# controller.net
KiCad netlist of a schematic drawn in EAGLE
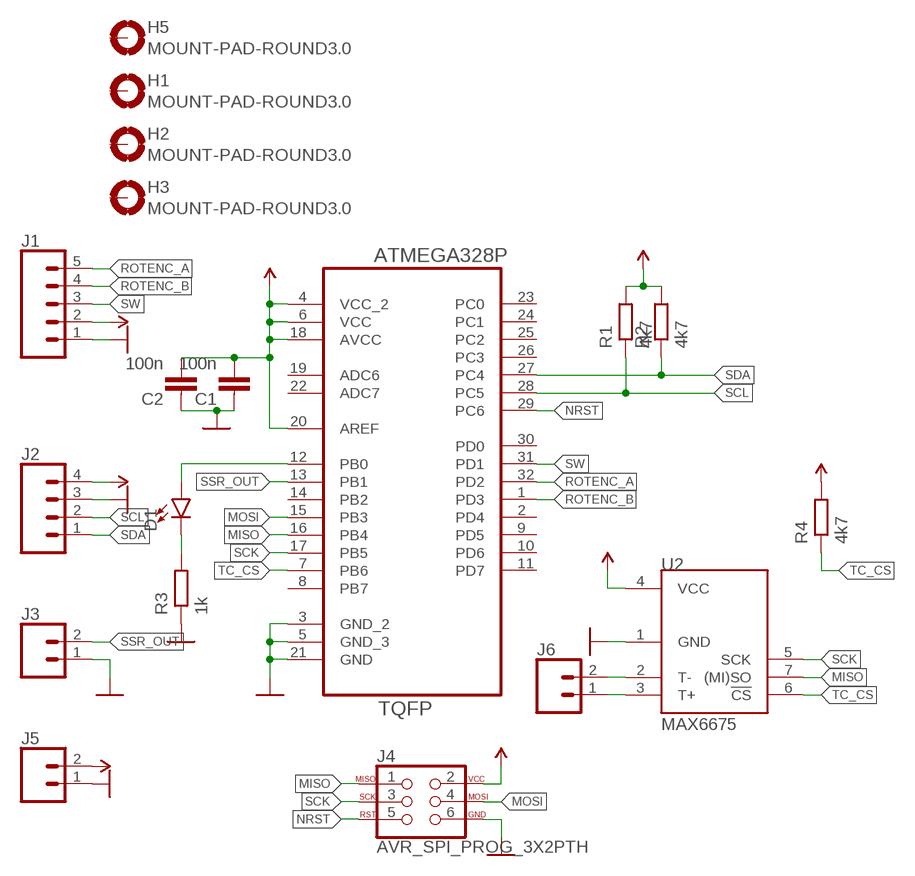
[diagram p0: schematic, sheet 1]

(export (version "E")
  (design (tool "Eeschema 10.0.6"))
  (components
    (comp (ref "C1")
      (value "100n")
      (footprint "eagle-import:C0603-N")
      (libsource (lib "eagle-import") (part "CAPACITOR0603-N"))
    )
    (comp (ref "C2")
      (value "100n")
      (footprint "eagle-import:C0603-N")
      (libsource (lib "eagle-import") (part "CAPACITOR0603-N"))
    )
    (comp (ref "D1")
      (value "LED0603")
      (footprint "eagle-import:LED-0603")
      (libsource (lib "eagle-import") (part "LED0603"))
    )
    (comp (ref "H1")
      (value "MOUNT-PAD-ROUND3.0")
      (footprint "eagle-import:3,0-PAD")
      (libsource (lib "eagle-import") (part "MOUNT-PAD-ROUND3.0"))
    )
    (comp (ref "H2")
      (value "MOUNT-PAD-ROUND3.0")
      (footprint "eagle-import:3,0-PAD")
      (libsource (lib "eagle-import") (part "MOUNT-PAD-ROUND3.0"))
    )
    (comp (ref "H3")
      (value "MOUNT-PAD-ROUND3.0")
      (footprint "eagle-import:3,0-PAD")
      (libsource (lib "eagle-import") (part "MOUNT-PAD-ROUND3.0"))
    )
    (comp (ref "H5")
      (value "MOUNT-PAD-ROUND3.0")
      (footprint "eagle-import:3,0-PAD")
      (libsource (lib "eagle-import") (part "MOUNT-PAD-ROUND3.0"))
    )
    (comp (ref "J1")
      (value "CONN_05PTH_LONGPADS")
      (footprint "eagle-import:1X05_LONGPADS")
      (libsource (lib "eagle-import") (part "CONN_05PTH_LONGPADS"))
    )
    (comp (ref "J2")
      (value "CONN_04LONGPADS")
      (footprint "eagle-import:1X04_LONGPADS")
      (libsource (lib "eagle-import") (part "CONN_04LONGPADS"))
    )
    (comp (ref "J3")
      (value "CONN_02PTH3")
      (footprint "eagle-import:1X02_LONGPADS")
      (libsource (lib "eagle-import") (part "CONN_02PTH3"))
    )
    (comp (ref "J4")
      (value "AVR_SPI_PROG_3X2PTH")
      (footprint "eagle-import:2X3")
      (libsource (lib "eagle-import") (part "AVR_SPI_PROG_3X2PTH"))
    )
    (comp (ref "J5")
      (value "CONN_02PTH3")
      (footprint "eagle-import:1X02_LONGPADS")
      (libsource (lib "eagle-import") (part "CONN_02PTH3"))
    )
    (comp (ref "J6")
      (value "CONN_02PTH3")
      (footprint "eagle-import:1X02_LONGPADS")
      (libsource (lib "eagle-import") (part "CONN_02PTH3"))
    )
    (comp (ref "R1")
      (value "4k7")
      (footprint "eagle-import:R0603-N")
      (libsource (lib "eagle-import") (part "RESISTOR0603-N"))
    )
    (comp (ref "R2")
      (value "4k7")
      (footprint "eagle-import:R0603-N")
      (libsource (lib "eagle-import") (part "RESISTOR0603-N"))
    )
    (comp (ref "R3")
      (value "1k")
      (footprint "eagle-import:R0603-N")
      (libsource (lib "eagle-import") (part "RESISTOR0603-N"))
    )
    (comp (ref "R4")
      (value "4k7")
      (footprint "eagle-import:R0603-N")
      (libsource (lib "eagle-import") (part "RESISTOR0603-N"))
    )
    (comp (ref "U1")
      (value "ATMEGA328P-AU")
      (footprint "eagle-import:QFP80P900X900X120-32N")
      (libsource (lib "eagle-import") (part "ATMEGA328P-AU"))
    )
    (comp (ref "U2")
      (value "MAX6675")
      (footprint "eagle-import:SOIC8")
      (libsource (lib "eagle-import") (part "MAX6675"))
    )
  )
  (nets
    (net (code "1") (name "GND") (class "Default")
      (node (ref "C1") (pin "1") (pinfunction "1_1") (pintype "passive"))
      (node (ref "C2") (pin "1") (pinfunction "1_1") (pintype "passive"))
      (node (ref "J1") (pin "1") (pinfunction "1_1") (pintype "passive"))
      (node (ref "J2") (pin "3") (pinfunction "3_3") (pintype "passive"))
      (node (ref "J3") (pin "1") (pinfunction "1_1") (pintype "passive"))
      (node (ref "J4") (pin "6") (pinfunction "6_6") (pintype "passive"))
      (node (ref "J5") (pin "1") (pinfunction "1_1") (pintype "passive"))
      (node (ref "R3") (pin "1") (pinfunction "P$1_1") (pintype "passive"))
      (node (ref "U1") (pin "21") (pinfunction "GND_21") (pintype "passive"))
      (node (ref "U1") (pin "3") (pinfunction "GND_2_3") (pintype "passive"))
      (node (ref "U1") (pin "5") (pinfunction "GND_3_5") (pintype "passive"))
      (node (ref "U2") (pin "1") (pinfunction "GND_1") (pintype "bidirectional"))
    )
    (net (code "2") (name "MISO") (class "Default")
      (node (ref "J4") (pin "1") (pinfunction "1_1") (pintype "passive"))
      (node (ref "U1") (pin "16") (pinfunction "PB4_16") (pintype "bidirectional"))
      (node (ref "U2") (pin "7") (pinfunction "(MI)SO_7") (pintype "bidirectional"))
    )
    (net (code "3") (name "MOSI") (class "Default")
      (node (ref "J4") (pin "4") (pinfunction "4_4") (pintype "passive"))
      (node (ref "U1") (pin "15") (pinfunction "PB3_15") (pintype "bidirectional"))
    )
    (net (code "4") (name "NRST") (class "Default")
      (node (ref "J4") (pin "5") (pinfunction "5_5") (pintype "passive"))
      (node (ref "U1") (pin "29") (pinfunction "PC6_29") (pintype "bidirectional"))
    )
    (net (code "5") (name "Net-(R3-P$2)") (class "Default")
      (node (ref "D1") (pin "C") (pinfunction "C_C") (pintype "passive"))
      (node (ref "R3") (pin "2") (pinfunction "P$2_2") (pintype "passive"))
    )
    (net (code "6") (name "Net-(U1-PB0)") (class "Default")
      (node (ref "D1") (pin "A") (pinfunction "A_A") (pintype "passive"))
      (node (ref "U1") (pin "12") (pinfunction "PB0_12") (pintype "bidirectional"))
    )
    (net (code "7") (name "Net-(U2-T+)") (class "Default")
      (node (ref "J6") (pin "1") (pinfunction "1_1") (pintype "passive"))
      (node (ref "U2") (pin "3") (pinfunction "T+_3") (pintype "bidirectional"))
    )
    (net (code "8") (name "Net-(U2-T-)") (class "Default")
      (node (ref "J6") (pin "2") (pinfunction "2_2") (pintype "passive"))
      (node (ref "U2") (pin "2") (pinfunction "T-_2") (pintype "bidirectional"))
    )
    (net (code "9") (name "ROTENC_A") (class "Default")
      (node (ref "J1") (pin "5") (pinfunction "5_5") (pintype "passive"))
      (node (ref "U1") (pin "32") (pinfunction "PD2_32") (pintype "bidirectional"))
    )
    (net (code "10") (name "ROTENC_B") (class "Default")
      (node (ref "J1") (pin "4") (pinfunction "4_4") (pintype "passive"))
      (node (ref "U1") (pin "1") (pinfunction "PD3_1") (pintype "bidirectional"))
    )
    (net (code "11") (name "SCK") (class "Default")
      (node (ref "J4") (pin "3") (pinfunction "3_3") (pintype "passive"))
      (node (ref "U1") (pin "17") (pinfunction "PB5_17") (pintype "bidirectional"))
      (node (ref "U2") (pin "5") (pinfunction "SCK_5") (pintype "bidirectional"))
    )
    (net (code "12") (name "SCL") (class "Default")
      (node (ref "J2") (pin "2") (pinfunction "2_2") (pintype "passive"))
      (node (ref "R1") (pin "1") (pinfunction "P$1_1") (pintype "passive"))
      (node (ref "U1") (pin "28") (pinfunction "PC5_28") (pintype "bidirectional"))
    )
    (net (code "13") (name "SDA") (class "Default")
      (node (ref "J2") (pin "1") (pinfunction "1_1") (pintype "passive"))
      (node (ref "R2") (pin "1") (pinfunction "P$1_1") (pintype "passive"))
      (node (ref "U1") (pin "27") (pinfunction "PC4_27") (pintype "bidirectional"))
    )
    (net (code "14") (name "SSR_OUT") (class "Default")
      (node (ref "J3") (pin "2") (pinfunction "2_2") (pintype "passive"))
      (node (ref "U1") (pin "13") (pinfunction "PB1_13") (pintype "bidirectional"))
    )
    (net (code "15") (name "SW") (class "Default")
      (node (ref "J1") (pin "3") (pinfunction "3_3") (pintype "passive"))
      (node (ref "U1") (pin "31") (pinfunction "PD1_31") (pintype "bidirectional"))
    )
    (net (code "16") (name "TC_CS") (class "Default")
      (node (ref "R4") (pin "1") (pinfunction "P$1_1") (pintype "passive"))
      (node (ref "U1") (pin "7") (pinfunction "PB6_7") (pintype "bidirectional"))
      (node (ref "U2") (pin "6") (pinfunction "~{CS}_6") (pintype "bidirectional"))
    )
    (net (code "17") (name "VCC") (class "Default")
      (node (ref "C1") (pin "2") (pinfunction "2_2") (pintype "passive"))
      (node (ref "C2") (pin "2") (pinfunction "2_2") (pintype "passive"))
      (node (ref "J1") (pin "2") (pinfunction "2_2") (pintype "passive"))
      (node (ref "J2") (pin "4") (pinfunction "4_4") (pintype "passive"))
      (node (ref "J4") (pin "2") (pinfunction "2_2") (pintype "passive"))
      (node (ref "J5") (pin "2") (pinfunction "2_2") (pintype "passive"))
      (node (ref "R1") (pin "2") (pinfunction "P$2_2") (pintype "passive"))
      (node (ref "R2") (pin "2") (pinfunction "P$2_2") (pintype "passive"))
      (node (ref "R4") (pin "2") (pinfunction "P$2_2") (pintype "passive"))
      (node (ref "U1") (pin "18") (pinfunction "AVCC_18") (pintype "power_in"))
      (node (ref "U1") (pin "20") (pinfunction "AREF_20") (pintype "input"))
      (node (ref "U1") (pin "4") (pinfunction "VCC_2_4") (pintype "power_in"))
      (node (ref "U1") (pin "6") (pinfunction "VCC_6") (pintype "power_in"))
      (node (ref "U2") (pin "4") (pinfunction "VCC_4") (pintype "bidirectional"))
    )
    (net (code "18") (name "unconnected-(H1-MOUNT-PadB3,0)") (class "Default")
      (node (ref "H1") (pin "B3,0") (pinfunction "MOUNT_B3,0") (pintype "passive"))
    )
    (net (code "19") (name "unconnected-(H2-MOUNT-PadB3,0)") (class "Default")
      (node (ref "H2") (pin "B3,0") (pinfunction "MOUNT_B3,0") (pintype "passive"))
    )
    (net (code "20") (name "unconnected-(H3-MOUNT-PadB3,0)") (class "Default")
      (node (ref "H3") (pin "B3,0") (pinfunction "MOUNT_B3,0") (pintype "passive"))
    )
    (net (code "21") (name "unconnected-(H5-MOUNT-PadB3,0)") (class "Default")
      (node (ref "H5") (pin "B3,0") (pinfunction "MOUNT_B3,0") (pintype "passive"))
    )
    (net (code "22") (name "unconnected-(U1-ADC6-Pad19)") (class "Default")
      (node (ref "U1") (pin "19") (pinfunction "ADC6_19") (pintype "input"))
    )
    (net (code "23") (name "unconnected-(U1-ADC7-Pad22)") (class "Default")
      (node (ref "U1") (pin "22") (pinfunction "ADC7_22") (pintype "input"))
    )
    (net (code "24") (name "unconnected-(U1-PB2-Pad14)") (class "Default")
      (node (ref "U1") (pin "14") (pinfunction "PB2_14") (pintype "bidirectional"))
    )
    (net (code "25") (name "unconnected-(U1-PB7-Pad8)") (class "Default")
      (node (ref "U1") (pin "8") (pinfunction "PB7_8") (pintype "bidirectional"))
    )
    (net (code "26") (name "unconnected-(U1-PC0-Pad23)") (class "Default")
      (node (ref "U1") (pin "23") (pinfunction "PC0_23") (pintype "bidirectional"))
    )
    (net (code "27") (name "unconnected-(U1-PC1-Pad24)") (class "Default")
      (node (ref "U1") (pin "24") (pinfunction "PC1_24") (pintype "bidirectional"))
    )
    (net (code "28") (name "unconnected-(U1-PC2-Pad25)") (class "Default")
      (node (ref "U1") (pin "25") (pinfunction "PC2_25") (pintype "bidirectional"))
    )
    (net (code "29") (name "unconnected-(U1-PC3-Pad26)") (class "Default")
      (node (ref "U1") (pin "26") (pinfunction "PC3_26") (pintype "bidirectional"))
    )
    (net (code "30") (name "unconnected-(U1-PD0-Pad30)") (class "Default")
      (node (ref "U1") (pin "30") (pinfunction "PD0_30") (pintype "bidirectional"))
    )
    (net (code "31") (name "unconnected-(U1-PD4-Pad2)") (class "Default")
      (node (ref "U1") (pin "2") (pinfunction "PD4_2") (pintype "bidirectional"))
    )
    (net (code "32") (name "unconnected-(U1-PD5-Pad9)") (class "Default")
      (node (ref "U1") (pin "9") (pinfunction "PD5_9") (pintype "bidirectional"))
    )
    (net (code "33") (name "unconnected-(U1-PD6-Pad10)") (class "Default")
      (node (ref "U1") (pin "10") (pinfunction "PD6_10") (pintype "bidirectional"))
    )
    (net (code "34") (name "unconnected-(U1-PD7-Pad11)") (class "Default")
      (node (ref "U1") (pin "11") (pinfunction "PD7_11") (pintype "bidirectional"))
    )
  )
)
